# schematic_easyeda.net
KiCad netlist of a schematic drawn in EasyEDA
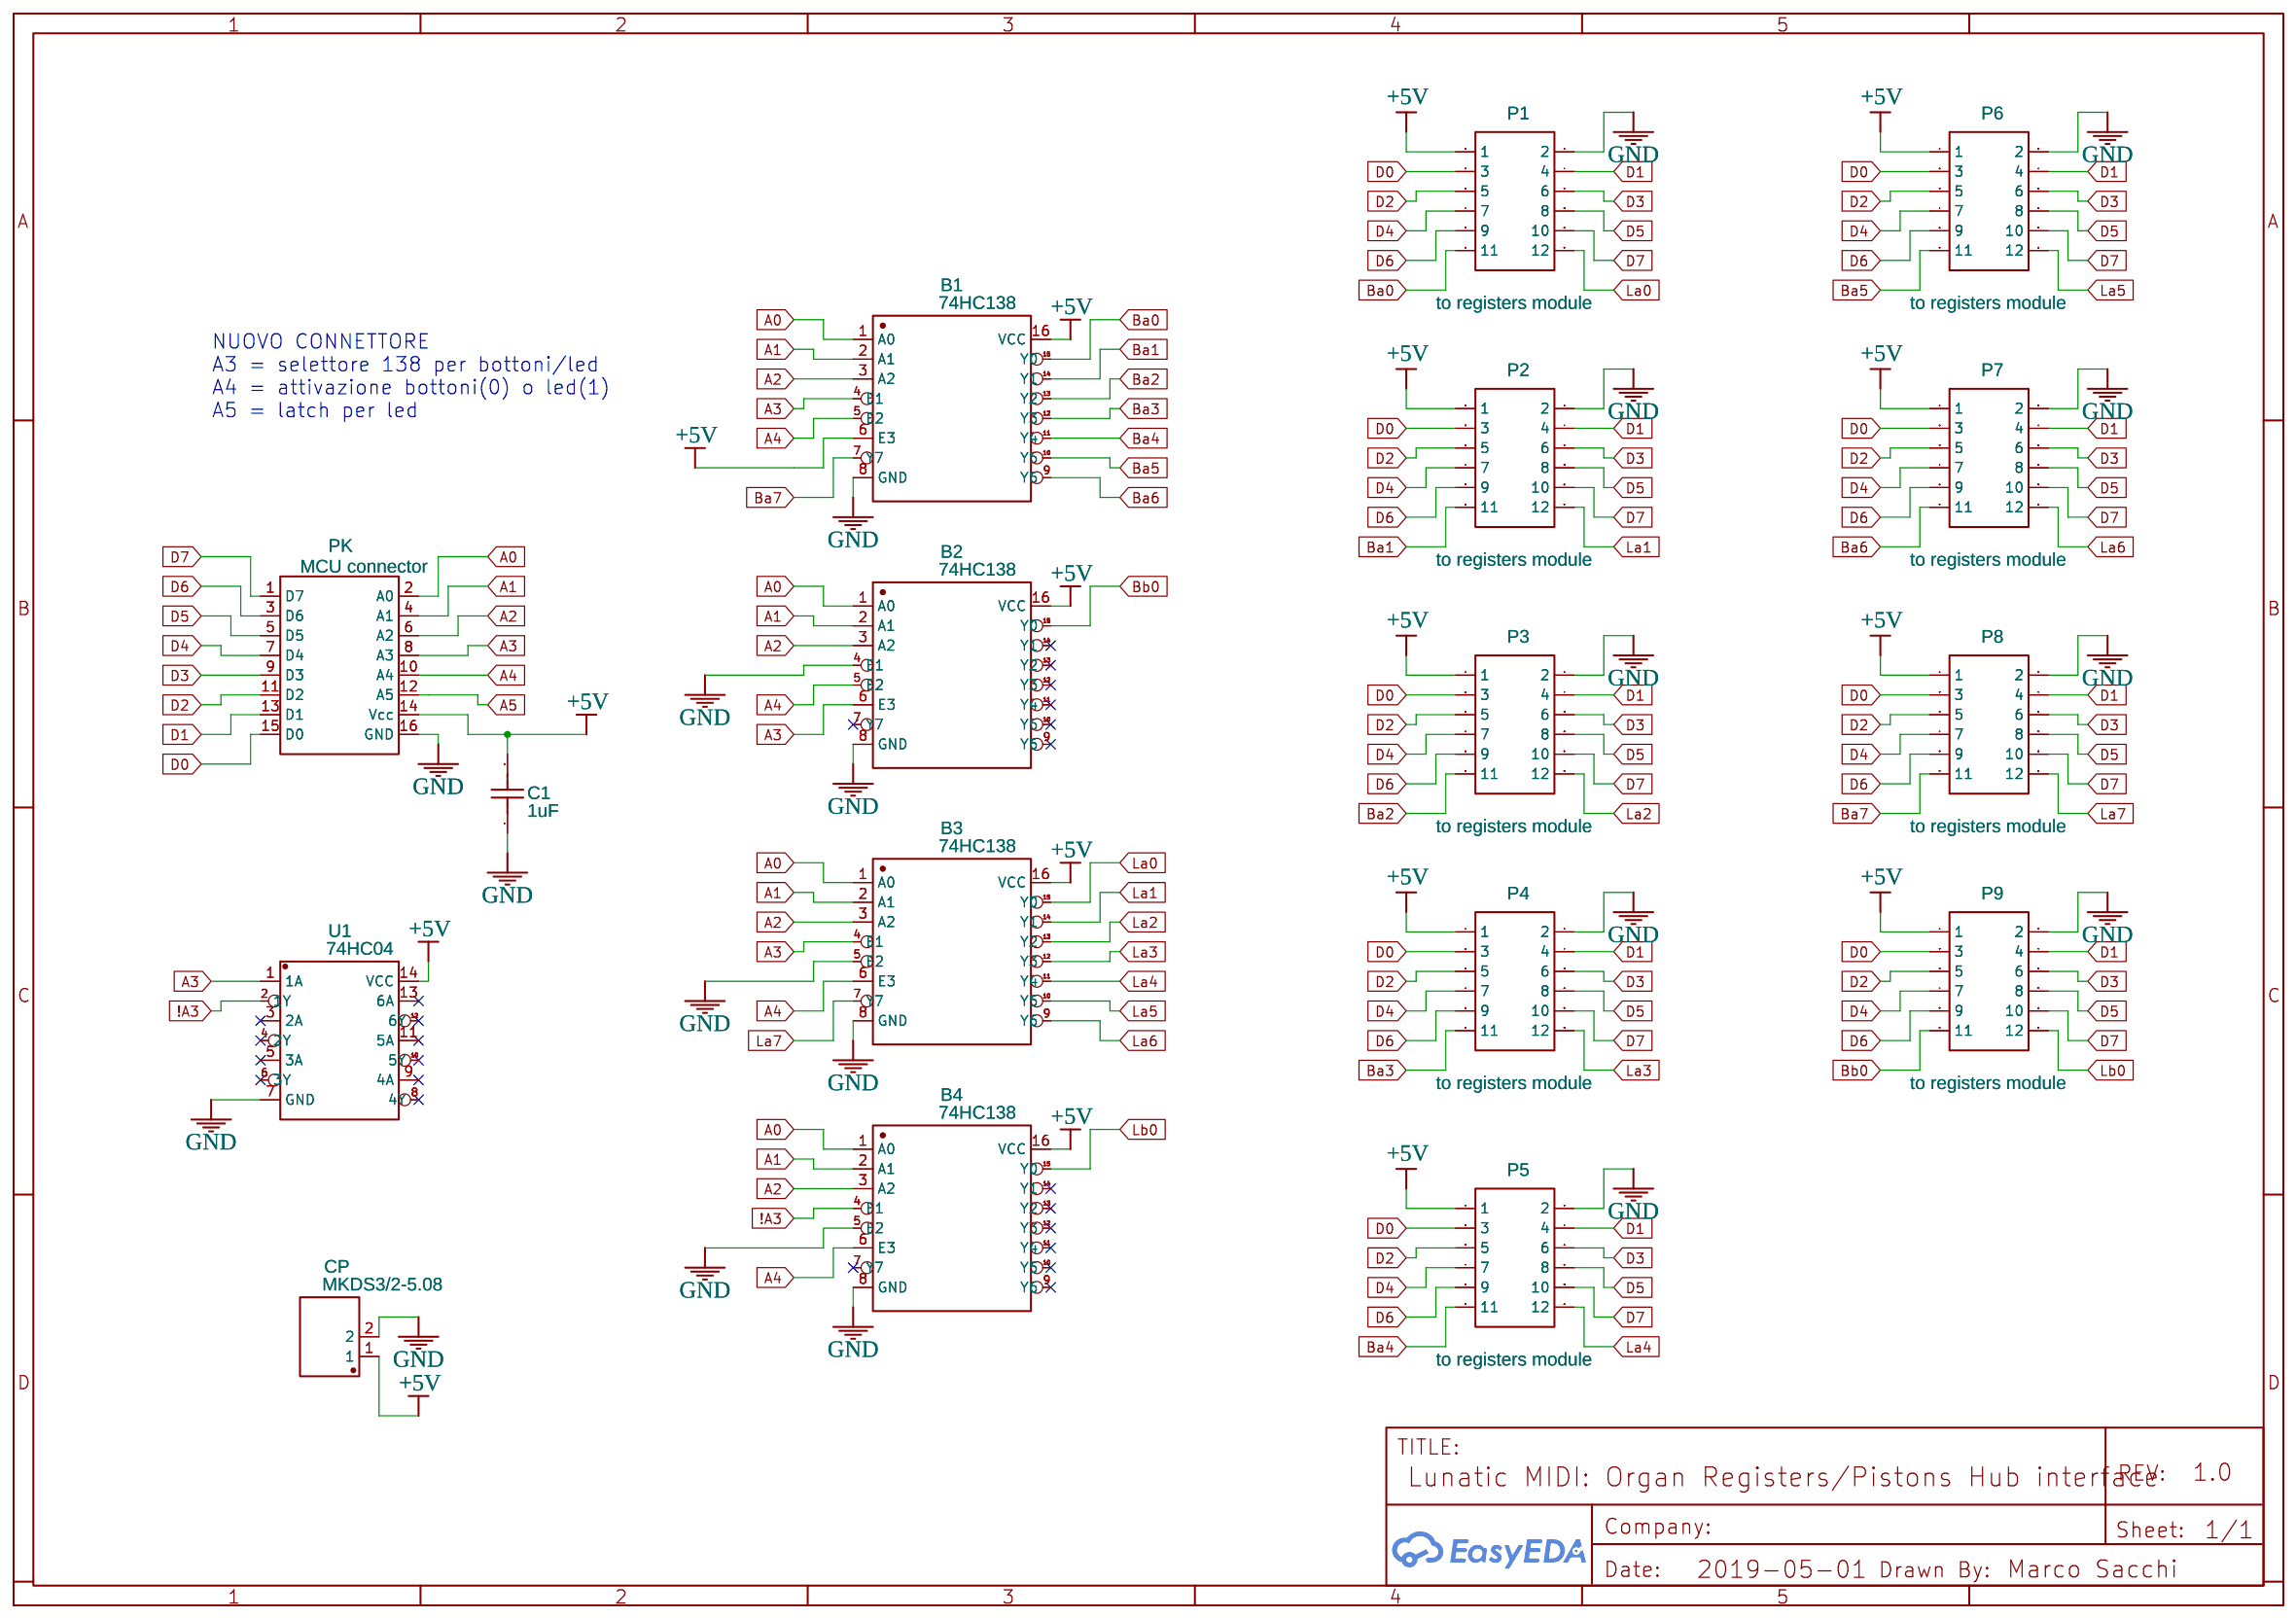
[diagram p0: schematic sheet]

(export (version "E")
  (design (tool "Eeschema 10.0.6"))
  (components
    (comp (ref "B1")
      (value "74HC138")
      (fields (field (name "BOM_Supplier Part") "C5194"))
      (libsource (lib "") (part "Unknown_475_200"))
    )
    (comp (ref "B2")
      (value "74HC138")
      (fields (field (name "BOM_Supplier Part") "C5194"))
      (libsource (lib "") (part "Unknown_475_335"))
    )
    (comp (ref "B3")
      (value "74HC138")
      (fields (field (name "BOM_Supplier Part") "C5194"))
      (libsource (lib "") (part "Unknown_475_475"))
    )
    (comp (ref "B4")
      (value "74HC138")
      (fields (field (name "BOM_Supplier Part") "C5194"))
      (libsource (lib "") (part "Unknown_475_610"))
    )
    (comp (ref "C1")
      (value "1uF")
      (fields (field (name "BOM_Manufacturer Part") "?"))
      (libsource (lib "") (part "Cap_RAD-0.1_US"))
    )
    (comp (ref "CP")
      (value "MKDS3/2-5.08")
      (fields (field (name "BOM_Supplier Part") "C89120"))
      (libsource (lib "") (part "Unknown_165_670"))
    )
    (comp (ref "P1")
      (value "to registers module")
      (fields (field (name "BOM_Manufacturer Part") "?") (field (name "BOM_Supplier Part") "C66689"))
      (libsource (lib "") (part "Unknown_760_95"))
    )
    (comp (ref "P2")
      (value "to registers module")
      (fields (field (name "BOM_Manufacturer Part") "?") (field (name "BOM_Supplier Part") "C66689"))
      (libsource (lib "") (part "Unknown_760_225"))
    )
    (comp (ref "P3")
      (value "to registers module")
      (fields (field (name "BOM_Manufacturer Part") "?") (field (name "BOM_Supplier Part") "C66689"))
      (libsource (lib "") (part "Unknown_760_360"))
    )
    (comp (ref "P4")
      (value "to registers module")
      (fields (field (name "BOM_Manufacturer Part") "?") (field (name "BOM_Supplier Part") "C66689"))
      (libsource (lib "") (part "Unknown_760_490"))
    )
    (comp (ref "P5")
      (value "to registers module")
      (fields (field (name "BOM_Manufacturer Part") "?") (field (name "BOM_Supplier Part") "C66689"))
      (libsource (lib "") (part "Unknown_760_630"))
    )
    (comp (ref "P6")
      (value "to registers module")
      (fields (field (name "BOM_Manufacturer Part") "?") (field (name "BOM_Supplier Part") "C66689"))
      (libsource (lib "") (part "Unknown_1000_95"))
    )
    (comp (ref "P7")
      (value "to registers module")
      (fields (field (name "BOM_Manufacturer Part") "?") (field (name "BOM_Supplier Part") "C66689"))
      (libsource (lib "") (part "Unknown_1000_225"))
    )
    (comp (ref "P8")
      (value "to registers module")
      (fields (field (name "BOM_Manufacturer Part") "?") (field (name "BOM_Supplier Part") "C66689"))
      (libsource (lib "") (part "Unknown_1000_360"))
    )
    (comp (ref "P9")
      (value "to registers module")
      (fields (field (name "BOM_Manufacturer Part") "?") (field (name "BOM_Supplier Part") "C66689"))
      (libsource (lib "") (part "Unknown_1000_490"))
    )
    (comp (ref "PK")
      (value "MCU connector")
      (fields (field (name "BOM_Manufacturer Part") "GEM"))
      (libsource (lib "") (part "Unknown_155_325"))
    )
    (comp (ref "U1")
      (value "74HC04")
      (fields (field (name "BOM_Supplier Part") "C192161"))
      (libsource (lib "") (part "Unknown_165_520"))
    )
  )
  (nets
    (net (code "1") (name "!A3") (class "Default")
      (node (ref "B4") (pin "4") (pinfunction "E1_4") (pintype "unspecified"))
      (node (ref "U1") (pin "2") (pinfunction "1Y_2") (pintype "unspecified"))
    )
    (net (code "2") (name "+5V") (class "Default")
      (node (ref "B1") (pin "16") (pinfunction "VCC_16") (pintype "unspecified"))
      (node (ref "B1") (pin "6") (pinfunction "E3_6") (pintype "unspecified"))
      (node (ref "B2") (pin "16") (pinfunction "VCC_16") (pintype "unspecified"))
      (node (ref "B3") (pin "16") (pinfunction "VCC_16") (pintype "unspecified"))
      (node (ref "B4") (pin "16") (pinfunction "VCC_16") (pintype "unspecified"))
      (node (ref "C1") (pin "2") (pinfunction "2_2") (pintype "unspecified"))
      (node (ref "CP") (pin "1") (pinfunction "1_1") (pintype "unspecified"))
      (node (ref "P1") (pin "1") (pinfunction "1_1") (pintype "input"))
      (node (ref "P2") (pin "1") (pinfunction "1_1") (pintype "input"))
      (node (ref "P3") (pin "1") (pinfunction "1_1") (pintype "input"))
      (node (ref "P4") (pin "1") (pinfunction "1_1") (pintype "input"))
      (node (ref "P5") (pin "1") (pinfunction "1_1") (pintype "input"))
      (node (ref "P6") (pin "1") (pinfunction "1_1") (pintype "input"))
      (node (ref "P7") (pin "1") (pinfunction "1_1") (pintype "input"))
      (node (ref "P8") (pin "1") (pinfunction "1_1") (pintype "input"))
      (node (ref "P9") (pin "1") (pinfunction "1_1") (pintype "input"))
      (node (ref "PK") (pin "14") (pinfunction "Vcc_14") (pintype "passive"))
      (node (ref "U1") (pin "14") (pinfunction "VCC_14") (pintype "unspecified"))
    )
    (net (code "3") (name "A0") (class "Default")
      (node (ref "B1") (pin "1") (pinfunction "A0_1") (pintype "unspecified"))
      (node (ref "B2") (pin "1") (pinfunction "A0_1") (pintype "unspecified"))
      (node (ref "B3") (pin "1") (pinfunction "A0_1") (pintype "unspecified"))
      (node (ref "B4") (pin "1") (pinfunction "A0_1") (pintype "unspecified"))
      (node (ref "PK") (pin "2") (pinfunction "A0_2") (pintype "output"))
    )
    (net (code "4") (name "A1") (class "Default")
      (node (ref "B1") (pin "2") (pinfunction "A1_2") (pintype "unspecified"))
      (node (ref "B2") (pin "2") (pinfunction "A1_2") (pintype "unspecified"))
      (node (ref "B3") (pin "2") (pinfunction "A1_2") (pintype "unspecified"))
      (node (ref "B4") (pin "2") (pinfunction "A1_2") (pintype "unspecified"))
      (node (ref "PK") (pin "4") (pinfunction "A1_4") (pintype "output"))
    )
    (net (code "5") (name "A2") (class "Default")
      (node (ref "B1") (pin "3") (pinfunction "A2_3") (pintype "unspecified"))
      (node (ref "B2") (pin "3") (pinfunction "A2_3") (pintype "unspecified"))
      (node (ref "B3") (pin "3") (pinfunction "A2_3") (pintype "unspecified"))
      (node (ref "B4") (pin "3") (pinfunction "A2_3") (pintype "unspecified"))
      (node (ref "PK") (pin "6") (pinfunction "A2_6") (pintype "output"))
    )
    (net (code "6") (name "A3") (class "Default")
      (node (ref "B1") (pin "4") (pinfunction "E1_4") (pintype "unspecified"))
      (node (ref "B2") (pin "6") (pinfunction "E3_6") (pintype "unspecified"))
      (node (ref "B3") (pin "4") (pinfunction "E1_4") (pintype "unspecified"))
      (node (ref "PK") (pin "8") (pinfunction "A3_8") (pintype "output"))
      (node (ref "U1") (pin "1") (pinfunction "1A_1") (pintype "unspecified"))
    )
    (net (code "7") (name "A4") (class "Default")
      (node (ref "B1") (pin "5") (pinfunction "E2_5") (pintype "unspecified"))
      (node (ref "B2") (pin "5") (pinfunction "E2_5") (pintype "unspecified"))
      (node (ref "B3") (pin "6") (pinfunction "E3_6") (pintype "unspecified"))
      (node (ref "B4") (pin "6") (pinfunction "E3_6") (pintype "unspecified"))
      (node (ref "PK") (pin "10") (pinfunction "A4_10") (pintype "output"))
    )
    (net (code "8") (name "A5") (class "Default")
      (node (ref "PK") (pin "12") (pinfunction "A5_12") (pintype "output"))
    )
    (net (code "9") (name "Ba0") (class "Default")
      (node (ref "B1") (pin "15") (pinfunction "Y0_15") (pintype "unspecified"))
      (node (ref "P1") (pin "11") (pinfunction "11_11") (pintype "input"))
    )
    (net (code "10") (name "Ba1") (class "Default")
      (node (ref "B1") (pin "14") (pinfunction "Y1_14") (pintype "unspecified"))
      (node (ref "P2") (pin "11") (pinfunction "11_11") (pintype "input"))
    )
    (net (code "11") (name "Ba2") (class "Default")
      (node (ref "B1") (pin "13") (pinfunction "Y2_13") (pintype "unspecified"))
      (node (ref "P3") (pin "11") (pinfunction "11_11") (pintype "input"))
    )
    (net (code "12") (name "Ba3") (class "Default")
      (node (ref "B1") (pin "12") (pinfunction "Y3_12") (pintype "unspecified"))
      (node (ref "P4") (pin "11") (pinfunction "11_11") (pintype "input"))
    )
    (net (code "13") (name "Ba4") (class "Default")
      (node (ref "B1") (pin "11") (pinfunction "Y4_11") (pintype "unspecified"))
      (node (ref "P5") (pin "11") (pinfunction "11_11") (pintype "input"))
    )
    (net (code "14") (name "Ba5") (class "Default")
      (node (ref "B1") (pin "10") (pinfunction "Y5_10") (pintype "unspecified"))
      (node (ref "P6") (pin "11") (pinfunction "11_11") (pintype "input"))
    )
    (net (code "15") (name "Ba6") (class "Default")
      (node (ref "B1") (pin "9") (pinfunction "Y6_9") (pintype "unspecified"))
      (node (ref "P7") (pin "11") (pinfunction "11_11") (pintype "input"))
    )
    (net (code "16") (name "Ba7") (class "Default")
      (node (ref "B1") (pin "7") (pinfunction "Y7_7") (pintype "unspecified"))
      (node (ref "P8") (pin "11") (pinfunction "11_11") (pintype "input"))
    )
    (net (code "17") (name "Bb0") (class "Default")
      (node (ref "B2") (pin "15") (pinfunction "Y0_15") (pintype "unspecified"))
      (node (ref "P9") (pin "11") (pinfunction "11_11") (pintype "input"))
    )
    (net (code "18") (name "D0") (class "Default")
      (node (ref "P1") (pin "3") (pinfunction "3_3") (pintype "input"))
      (node (ref "P2") (pin "3") (pinfunction "3_3") (pintype "input"))
      (node (ref "P3") (pin "3") (pinfunction "3_3") (pintype "input"))
      (node (ref "P4") (pin "3") (pinfunction "3_3") (pintype "input"))
      (node (ref "P5") (pin "3") (pinfunction "3_3") (pintype "input"))
      (node (ref "P6") (pin "3") (pinfunction "3_3") (pintype "input"))
      (node (ref "P7") (pin "3") (pinfunction "3_3") (pintype "input"))
      (node (ref "P8") (pin "3") (pinfunction "3_3") (pintype "input"))
      (node (ref "P9") (pin "3") (pinfunction "3_3") (pintype "input"))
      (node (ref "PK") (pin "15") (pinfunction "D0_15") (pintype "bidirectional"))
    )
    (net (code "19") (name "D1") (class "Default")
      (node (ref "P1") (pin "4") (pinfunction "4_4") (pintype "input"))
      (node (ref "P2") (pin "4") (pinfunction "4_4") (pintype "input"))
      (node (ref "P3") (pin "4") (pinfunction "4_4") (pintype "input"))
      (node (ref "P4") (pin "4") (pinfunction "4_4") (pintype "input"))
      (node (ref "P5") (pin "4") (pinfunction "4_4") (pintype "input"))
      (node (ref "P6") (pin "4") (pinfunction "4_4") (pintype "input"))
      (node (ref "P7") (pin "4") (pinfunction "4_4") (pintype "input"))
      (node (ref "P8") (pin "4") (pinfunction "4_4") (pintype "input"))
      (node (ref "P9") (pin "4") (pinfunction "4_4") (pintype "input"))
      (node (ref "PK") (pin "13") (pinfunction "D1_13") (pintype "bidirectional"))
    )
    (net (code "20") (name "D2") (class "Default")
      (node (ref "P1") (pin "5") (pinfunction "5_5") (pintype "input"))
      (node (ref "P2") (pin "5") (pinfunction "5_5") (pintype "input"))
      (node (ref "P3") (pin "5") (pinfunction "5_5") (pintype "input"))
      (node (ref "P4") (pin "5") (pinfunction "5_5") (pintype "input"))
      (node (ref "P5") (pin "5") (pinfunction "5_5") (pintype "input"))
      (node (ref "P6") (pin "5") (pinfunction "5_5") (pintype "input"))
      (node (ref "P7") (pin "5") (pinfunction "5_5") (pintype "input"))
      (node (ref "P8") (pin "5") (pinfunction "5_5") (pintype "input"))
      (node (ref "P9") (pin "5") (pinfunction "5_5") (pintype "input"))
      (node (ref "PK") (pin "11") (pinfunction "D2_11") (pintype "bidirectional"))
    )
    (net (code "21") (name "D3") (class "Default")
      (node (ref "P1") (pin "6") (pinfunction "6_6") (pintype "input"))
      (node (ref "P2") (pin "6") (pinfunction "6_6") (pintype "input"))
      (node (ref "P3") (pin "6") (pinfunction "6_6") (pintype "input"))
      (node (ref "P4") (pin "6") (pinfunction "6_6") (pintype "input"))
      (node (ref "P5") (pin "6") (pinfunction "6_6") (pintype "input"))
      (node (ref "P6") (pin "6") (pinfunction "6_6") (pintype "input"))
      (node (ref "P7") (pin "6") (pinfunction "6_6") (pintype "input"))
      (node (ref "P8") (pin "6") (pinfunction "6_6") (pintype "input"))
      (node (ref "P9") (pin "6") (pinfunction "6_6") (pintype "input"))
      (node (ref "PK") (pin "9") (pinfunction "D3_9") (pintype "bidirectional"))
    )
    (net (code "22") (name "D4") (class "Default")
      (node (ref "P1") (pin "7") (pinfunction "7_7") (pintype "input"))
      (node (ref "P2") (pin "7") (pinfunction "7_7") (pintype "input"))
      (node (ref "P3") (pin "7") (pinfunction "7_7") (pintype "input"))
      (node (ref "P4") (pin "7") (pinfunction "7_7") (pintype "input"))
      (node (ref "P5") (pin "7") (pinfunction "7_7") (pintype "input"))
      (node (ref "P6") (pin "7") (pinfunction "7_7") (pintype "input"))
      (node (ref "P7") (pin "7") (pinfunction "7_7") (pintype "input"))
      (node (ref "P8") (pin "7") (pinfunction "7_7") (pintype "input"))
      (node (ref "P9") (pin "7") (pinfunction "7_7") (pintype "input"))
      (node (ref "PK") (pin "7") (pinfunction "D4_7") (pintype "bidirectional"))
    )
    (net (code "23") (name "D5") (class "Default")
      (node (ref "P1") (pin "8") (pinfunction "8_8") (pintype "input"))
      (node (ref "P2") (pin "8") (pinfunction "8_8") (pintype "input"))
      (node (ref "P3") (pin "8") (pinfunction "8_8") (pintype "input"))
      (node (ref "P4") (pin "8") (pinfunction "8_8") (pintype "input"))
      (node (ref "P5") (pin "8") (pinfunction "8_8") (pintype "input"))
      (node (ref "P6") (pin "8") (pinfunction "8_8") (pintype "input"))
      (node (ref "P7") (pin "8") (pinfunction "8_8") (pintype "input"))
      (node (ref "P8") (pin "8") (pinfunction "8_8") (pintype "input"))
      (node (ref "P9") (pin "8") (pinfunction "8_8") (pintype "input"))
      (node (ref "PK") (pin "5") (pinfunction "D5_5") (pintype "bidirectional"))
    )
    (net (code "24") (name "D6") (class "Default")
      (node (ref "P1") (pin "9") (pinfunction "9_9") (pintype "input"))
      (node (ref "P2") (pin "9") (pinfunction "9_9") (pintype "input"))
      (node (ref "P3") (pin "9") (pinfunction "9_9") (pintype "input"))
      (node (ref "P4") (pin "9") (pinfunction "9_9") (pintype "input"))
      (node (ref "P5") (pin "9") (pinfunction "9_9") (pintype "input"))
      (node (ref "P6") (pin "9") (pinfunction "9_9") (pintype "input"))
      (node (ref "P7") (pin "9") (pinfunction "9_9") (pintype "input"))
      (node (ref "P8") (pin "9") (pinfunction "9_9") (pintype "input"))
      (node (ref "P9") (pin "9") (pinfunction "9_9") (pintype "input"))
      (node (ref "PK") (pin "3") (pinfunction "D6_3") (pintype "bidirectional"))
    )
    (net (code "25") (name "D7") (class "Default")
      (node (ref "P1") (pin "10") (pinfunction "10_10") (pintype "input"))
      (node (ref "P2") (pin "10") (pinfunction "10_10") (pintype "input"))
      (node (ref "P3") (pin "10") (pinfunction "10_10") (pintype "input"))
      (node (ref "P4") (pin "10") (pinfunction "10_10") (pintype "input"))
      (node (ref "P5") (pin "10") (pinfunction "10_10") (pintype "input"))
      (node (ref "P6") (pin "10") (pinfunction "10_10") (pintype "input"))
      (node (ref "P7") (pin "10") (pinfunction "10_10") (pintype "input"))
      (node (ref "P8") (pin "10") (pinfunction "10_10") (pintype "input"))
      (node (ref "P9") (pin "10") (pinfunction "10_10") (pintype "input"))
      (node (ref "PK") (pin "1") (pinfunction "D7_1") (pintype "bidirectional"))
    )
    (net (code "26") (name "GND") (class "Default")
      (node (ref "B1") (pin "8") (pinfunction "GND_8") (pintype "unspecified"))
      (node (ref "B2") (pin "4") (pinfunction "E1_4") (pintype "unspecified"))
      (node (ref "B2") (pin "8") (pinfunction "GND_8") (pintype "unspecified"))
      (node (ref "B3") (pin "5") (pinfunction "E2_5") (pintype "unspecified"))
      (node (ref "B3") (pin "8") (pinfunction "GND_8") (pintype "unspecified"))
      (node (ref "B4") (pin "5") (pinfunction "E2_5") (pintype "unspecified"))
      (node (ref "B4") (pin "8") (pinfunction "GND_8") (pintype "unspecified"))
      (node (ref "C1") (pin "1") (pinfunction "1_1") (pintype "unspecified"))
      (node (ref "CP") (pin "2") (pinfunction "2_2") (pintype "unspecified"))
      (node (ref "P1") (pin "2") (pinfunction "2_2") (pintype "input"))
      (node (ref "P2") (pin "2") (pinfunction "2_2") (pintype "input"))
      (node (ref "P3") (pin "2") (pinfunction "2_2") (pintype "input"))
      (node (ref "P4") (pin "2") (pinfunction "2_2") (pintype "input"))
      (node (ref "P5") (pin "2") (pinfunction "2_2") (pintype "input"))
      (node (ref "P6") (pin "2") (pinfunction "2_2") (pintype "input"))
      (node (ref "P7") (pin "2") (pinfunction "2_2") (pintype "input"))
      (node (ref "P8") (pin "2") (pinfunction "2_2") (pintype "input"))
      (node (ref "P9") (pin "2") (pinfunction "2_2") (pintype "input"))
      (node (ref "PK") (pin "16") (pinfunction "GND_16") (pintype "passive"))
      (node (ref "U1") (pin "7") (pinfunction "GND_7") (pintype "unspecified"))
    )
    (net (code "27") (name "La0") (class "Default")
      (node (ref "B3") (pin "15") (pinfunction "Y0_15") (pintype "unspecified"))
      (node (ref "P1") (pin "12") (pinfunction "12_12") (pintype "input"))
    )
    (net (code "28") (name "La1") (class "Default")
      (node (ref "B3") (pin "14") (pinfunction "Y1_14") (pintype "unspecified"))
      (node (ref "P2") (pin "12") (pinfunction "12_12") (pintype "input"))
    )
    (net (code "29") (name "La2") (class "Default")
      (node (ref "B3") (pin "13") (pinfunction "Y2_13") (pintype "unspecified"))
      (node (ref "P3") (pin "12") (pinfunction "12_12") (pintype "input"))
    )
    (net (code "30") (name "La3") (class "Default")
      (node (ref "B3") (pin "12") (pinfunction "Y3_12") (pintype "unspecified"))
      (node (ref "P4") (pin "12") (pinfunction "12_12") (pintype "input"))
    )
    (net (code "31") (name "La4") (class "Default")
      (node (ref "B3") (pin "11") (pinfunction "Y4_11") (pintype "unspecified"))
      (node (ref "P5") (pin "12") (pinfunction "12_12") (pintype "input"))
    )
    (net (code "32") (name "La5") (class "Default")
      (node (ref "B3") (pin "10") (pinfunction "Y5_10") (pintype "unspecified"))
      (node (ref "P6") (pin "12") (pinfunction "12_12") (pintype "input"))
    )
    (net (code "33") (name "La6") (class "Default")
      (node (ref "B3") (pin "9") (pinfunction "Y6_9") (pintype "unspecified"))
      (node (ref "P7") (pin "12") (pinfunction "12_12") (pintype "input"))
    )
    (net (code "34") (name "La7") (class "Default")
      (node (ref "B3") (pin "7") (pinfunction "Y7_7") (pintype "unspecified"))
      (node (ref "P8") (pin "12") (pinfunction "12_12") (pintype "input"))
    )
    (net (code "35") (name "Lb0") (class "Default")
      (node (ref "B4") (pin "15") (pinfunction "Y0_15") (pintype "unspecified"))
      (node (ref "P9") (pin "12") (pinfunction "12_12") (pintype "input"))
    )
    (net (code "36") (name "unconnected-(B2-Y1-Pad14)") (class "Default")
      (node (ref "B2") (pin "14") (pinfunction "Y1_14") (pintype "unspecified+no_connect"))
    )
    (net (code "37") (name "unconnected-(B2-Y2-Pad13)") (class "Default")
      (node (ref "B2") (pin "13") (pinfunction "Y2_13") (pintype "unspecified+no_connect"))
    )
    (net (code "38") (name "unconnected-(B2-Y3-Pad12)") (class "Default")
      (node (ref "B2") (pin "12") (pinfunction "Y3_12") (pintype "unspecified+no_connect"))
    )
    (net (code "39") (name "unconnected-(B2-Y4-Pad11)") (class "Default")
      (node (ref "B2") (pin "11") (pinfunction "Y4_11") (pintype "unspecified+no_connect"))
    )
    (net (code "40") (name "unconnected-(B2-Y5-Pad10)") (class "Default")
      (node (ref "B2") (pin "10") (pinfunction "Y5_10") (pintype "unspecified+no_connect"))
    )
    (net (code "41") (name "unconnected-(B2-Y6-Pad9)") (class "Default")
      (node (ref "B2") (pin "9") (pinfunction "Y6_9") (pintype "unspecified+no_connect"))
    )
    (net (code "42") (name "unconnected-(B2-Y7-Pad7)") (class "Default")
      (node (ref "B2") (pin "7") (pinfunction "Y7_7") (pintype "unspecified+no_connect"))
    )
    (net (code "43") (name "unconnected-(B4-Y1-Pad14)") (class "Default")
      (node (ref "B4") (pin "14") (pinfunction "Y1_14") (pintype "unspecified+no_connect"))
    )
    (net (code "44") (name "unconnected-(B4-Y2-Pad13)") (class "Default")
      (node (ref "B4") (pin "13") (pinfunction "Y2_13") (pintype "unspecified+no_connect"))
    )
    (net (code "45") (name "unconnected-(B4-Y3-Pad12)") (class "Default")
      (node (ref "B4") (pin "12") (pinfunction "Y3_12") (pintype "unspecified+no_connect"))
    )
    (net (code "46") (name "unconnected-(B4-Y4-Pad11)") (class "Default")
      (node (ref "B4") (pin "11") (pinfunction "Y4_11") (pintype "unspecified+no_connect"))
    )
    (net (code "47") (name "unconnected-(B4-Y5-Pad10)") (class "Default")
      (node (ref "B4") (pin "10") (pinfunction "Y5_10") (pintype "unspecified+no_connect"))
    )
    (net (code "48") (name "unconnected-(B4-Y6-Pad9)") (class "Default")
      (node (ref "B4") (pin "9") (pinfunction "Y6_9") (pintype "unspecified+no_connect"))
    )
    (net (code "49") (name "unconnected-(B4-Y7-Pad7)") (class "Default")
      (node (ref "B4") (pin "7") (pinfunction "Y7_7") (pintype "unspecified+no_connect"))
    )
    (net (code "50") (name "unconnected-(U1-2A-Pad3)") (class "Default")
      (node (ref "U1") (pin "3") (pinfunction "2A_3") (pintype "unspecified+no_connect"))
    )
    (net (code "51") (name "unconnected-(U1-2Y-Pad4)") (class "Default")
      (node (ref "U1") (pin "4") (pinfunction "2Y_4") (pintype "unspecified+no_connect"))
    )
    (net (code "52") (name "unconnected-(U1-3A-Pad5)") (class "Default")
      (node (ref "U1") (pin "5") (pinfunction "3A_5") (pintype "unspecified+no_connect"))
    )
    (net (code "53") (name "unconnected-(U1-3Y-Pad6)") (class "Default")
      (node (ref "U1") (pin "6") (pinfunction "3Y_6") (pintype "unspecified+no_connect"))
    )
    (net (code "54") (name "unconnected-(U1-4A-Pad9)") (class "Default")
      (node (ref "U1") (pin "9") (pinfunction "4A_9") (pintype "unspecified+no_connect"))
    )
    (net (code "55") (name "unconnected-(U1-4Y-Pad8)") (class "Default")
      (node (ref "U1") (pin "8") (pinfunction "4Y_8") (pintype "unspecified+no_connect"))
    )
    (net (code "56") (name "unconnected-(U1-5A-Pad11)") (class "Default")
      (node (ref "U1") (pin "11") (pinfunction "5A_11") (pintype "unspecified+no_connect"))
    )
    (net (code "57") (name "unconnected-(U1-5Y-Pad10)") (class "Default")
      (node (ref "U1") (pin "10") (pinfunction "5Y_10") (pintype "unspecified+no_connect"))
    )
    (net (code "58") (name "unconnected-(U1-6A-Pad13)") (class "Default")
      (node (ref "U1") (pin "13") (pinfunction "6A_13") (pintype "unspecified+no_connect"))
    )
    (net (code "59") (name "unconnected-(U1-6Y-Pad12)") (class "Default")
      (node (ref "U1") (pin "12") (pinfunction "6Y_12") (pintype "unspecified+no_connect"))
    )
  )
)
